# FIO_M.net
KiCad netlist of a schematic drawn in EAGLE
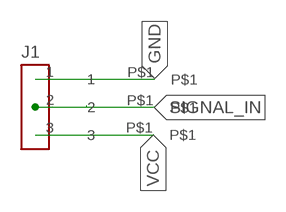
[diagram p0: schematic, sheet 1]

(export (version "E")
  (design (tool "Eeschema 10.0.6"))
  (components
    (comp (ref "J1")
      (value "CONECTOR_MACHO")
      (footprint "eagle-import:3CONECTOR")
      (libsource (lib "eagle-import") (part "CONECTOR_MACHO"))
    )
    (comp (ref "J3")
      (value "PAD")
      (footprint "eagle-import:PAD")
      (libsource (lib "eagle-import") (part "PAD"))
    )
    (comp (ref "U$1")
      (value "PAD")
      (footprint "eagle-import:PAD")
      (libsource (lib "eagle-import") (part "PAD"))
    )
    (comp (ref "VCC")
      (value "PAD")
      (footprint "eagle-import:PAD")
      (libsource (lib "eagle-import") (part "PAD"))
    )
  )
  (nets
    (net (code "1") (name "GND") (class "Default")
      (node (ref "J1") (pin "1") (pinfunction "1_1") (pintype "bidirectional"))
      (node (ref "U$1") (pin "P$1") (pinfunction "P$1_P$1") (pintype "bidirectional"))
    )
    (net (code "2") (name "SIGNAL_IN") (class "Default")
      (node (ref "J1") (pin "2") (pinfunction "2_2") (pintype "bidirectional"))
      (node (ref "J3") (pin "P$1") (pinfunction "P$1_P$1") (pintype "bidirectional"))
    )
    (net (code "3") (name "VCC") (class "Default")
      (node (ref "J1") (pin "3") (pinfunction "3_3") (pintype "bidirectional"))
      (node (ref "VCC") (pin "P$1") (pinfunction "P$1_P$1") (pintype "bidirectional"))
    )
  )
)
